# SmartRock_OsmoPod.net
KiCad netlist of a schematic drawn in EAGLE
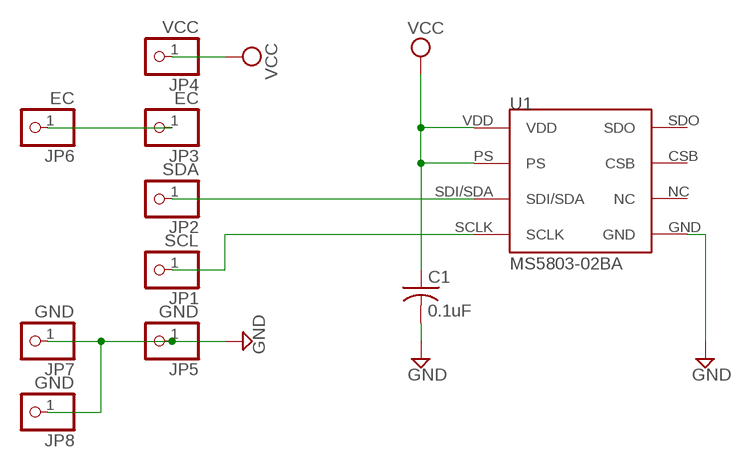
[diagram p0: schematic, sheet 1]

(export (version "E")
  (design (tool "Eeschema 10.0.6"))
  (components
    (comp (ref "C1")
      (value "0.1uF")
      (footprint "eagle-import:C1206")
      (libsource (lib "eagle-import") (part "C-USC1206"))
    )
    (comp (ref "JP1")
      (value "SCL")
      (footprint "eagle-import:1X01")
      (libsource (lib "eagle-import") (part "PINHD-1X1"))
    )
    (comp (ref "JP2")
      (value "SDA")
      (footprint "eagle-import:1X01")
      (libsource (lib "eagle-import") (part "PINHD-1X1"))
    )
    (comp (ref "JP3")
      (value "EC")
      (footprint "eagle-import:1X01")
      (libsource (lib "eagle-import") (part "PINHD-1X1"))
    )
    (comp (ref "JP4")
      (value "VCC")
      (footprint "eagle-import:1X01")
      (libsource (lib "eagle-import") (part "PINHD-1X1"))
    )
    (comp (ref "JP5")
      (value "GND")
      (footprint "eagle-import:1X01")
      (libsource (lib "eagle-import") (part "PINHD-1X1"))
    )
    (comp (ref "JP6")
      (value "EC")
      (footprint "eagle-import:1X01")
      (libsource (lib "eagle-import") (part "PINHD-1X1"))
    )
    (comp (ref "JP7")
      (value "GND")
      (footprint "eagle-import:1X01")
      (libsource (lib "eagle-import") (part "PINHD-1X1"))
    )
    (comp (ref "JP8")
      (value "GND")
      (footprint "eagle-import:1X01")
      (libsource (lib "eagle-import") (part "PINHD-1X1"))
    )
    (comp (ref "U1")
      (value "MS5803-02BA")
      (footprint "eagle-import:MS5803-02BA")
      (libsource (lib "eagle-import") (part "MS5803-02BA"))
    )
  )
  (nets
    (net (code "1") (name "GND") (class "Default")
      (node (ref "C1") (pin "2") (pinfunction "2_2") (pintype "passive"))
      (node (ref "JP5") (pin "1") (pinfunction "1_1") (pintype "passive"))
      (node (ref "JP7") (pin "1") (pinfunction "1_1") (pintype "passive"))
      (node (ref "JP8") (pin "1") (pinfunction "1_1") (pintype "passive"))
      (node (ref "U1") (pin "GND") (pinfunction "GND_GND") (pintype "bidirectional"))
    )
    (net (code "2") (name "Net-(JP1-Pad1)") (class "Default")
      (node (ref "JP1") (pin "1") (pinfunction "1_1") (pintype "passive"))
      (node (ref "U1") (pin "SCLK") (pinfunction "SCLK_SCLK") (pintype "bidirectional"))
    )
    (net (code "3") (name "Net-(JP2-Pad1)") (class "Default")
      (node (ref "JP2") (pin "1") (pinfunction "1_1") (pintype "passive"))
      (node (ref "U1") (pin "SDI/SDA") (pinfunction "SDI/SDA_SDI/SDA") (pintype "bidirectional"))
    )
    (net (code "4") (name "Net-(JP3-Pad1)") (class "Default")
      (node (ref "JP3") (pin "1") (pinfunction "1_1") (pintype "passive"))
      (node (ref "JP6") (pin "1") (pinfunction "1_1") (pintype "passive"))
    )
    (net (code "5") (name "VCC") (class "Default")
      (node (ref "C1") (pin "1") (pinfunction "1_1") (pintype "passive"))
      (node (ref "JP4") (pin "1") (pinfunction "1_1") (pintype "passive"))
      (node (ref "U1") (pin "PS") (pinfunction "PS_PS") (pintype "bidirectional"))
      (node (ref "U1") (pin "VDD") (pinfunction "VDD_VDD") (pintype "bidirectional"))
    )
    (net (code "6") (name "unconnected-(U1-PadCSB)") (class "Default")
      (node (ref "U1") (pin "CSB") (pinfunction "CSB_CSB") (pintype "bidirectional"))
    )
    (net (code "7") (name "unconnected-(U1-PadNC)") (class "Default")
      (node (ref "U1") (pin "NC") (pinfunction "NC_NC") (pintype "bidirectional"))
    )
    (net (code "8") (name "unconnected-(U1-PadSDO)") (class "Default")
      (node (ref "U1") (pin "SDO") (pinfunction "SDO_SDO") (pintype "bidirectional"))
    )
  )
)
